# Amp_Lm386.net
KiCad netlist of a schematic drawn in Altium Designer
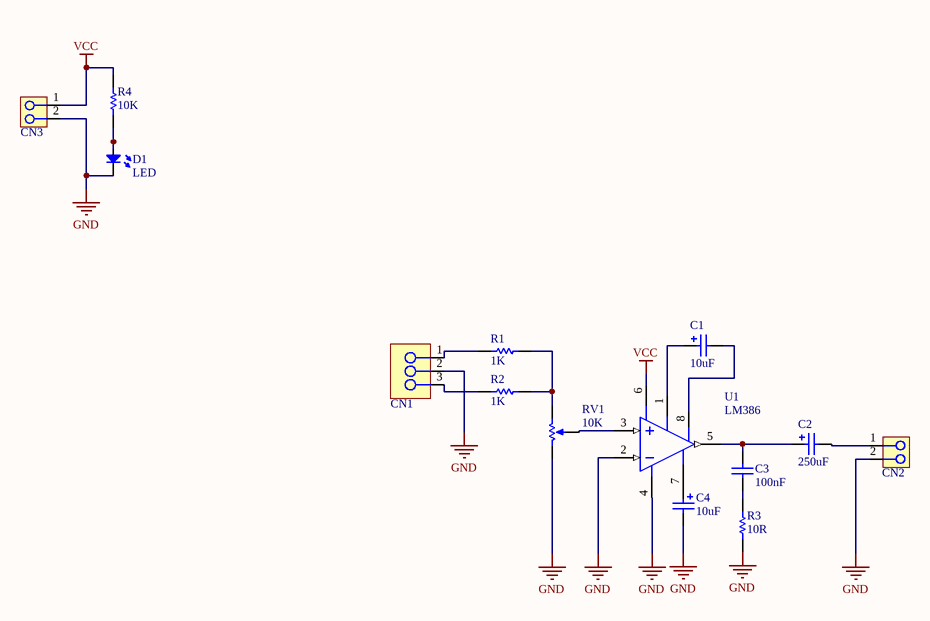
[diagram p0: Amp_Lm386.SchDoc]

(export (version "E")
  (design (tool "Eeschema 10.0.6"))
  (components
    (comp (ref "C1")
      (value "10uF")
      (footprint "Cap_1")
      (description "Capacitor Electrolytic")
      (fields
        (field (name "MANUFACTURER") "Nichicon")
        (field (name "MANUFACTURER PART NUMBER") "UCA2G100MPD1TD")
      )
      (libsource (lib "Adono_Library") (part "Cap_Eletro1"))
    )
    (comp (ref "C2")
      (value "250uF")
      (footprint "Cap_1")
      (description "Capacitor Electrolytic")
      (fields
        (field (name "MANUFACTURER") "Nichicon")
        (field (name "MANUFACTURER PART NUMBER") "UCA2G100MPD1TD")
      )
      (libsource (lib "Adono_Library") (part "Cap_Eletro1"))
    )
    (comp (ref "C3")
      (value "100nF")
      (footprint "CAP_DISC")
      (description "Capacitor Disc Ceramic")
      (fields
        (field (name "MANUFACTURER") "Multicomp")
        (field (name "MANUFACTURER PART NUMBER") "MCCC100V104KY5P")
      )
      (libsource (lib "Adono_Library") (part "Capacitor_Cerâmica"))
    )
    (comp (ref "C4")
      (value "10uF")
      (footprint "Cap_1")
      (description "Capacitor Electrolytic")
      (fields
        (field (name "MANUFACTURER") "Nichicon")
        (field (name "MANUFACTURER PART NUMBER") "UCA2G100MPD1TD")
      )
      (libsource (lib "Adono_Library") (part "Cap_Eletro1"))
    )
    (comp (ref "CN1")
      (value "H3")
      (footprint "H3")
      (description "KRE2/WD-128 3T")
      (fields
        (field (name "MANUFACTURER") "On-Shore Technology")
        (field (name "MANUFACTURER PART NUMBER") "OSTTA034163")
      )
      (libsource (lib "Adono_Library2") (part "H3"))
    )
    (comp (ref "CN2")
      (value "H2")
      (footprint "H2")
      (description "KRE2/WD-128 2T")
      (fields
        (field (name "MANUFACTURER") "On-Shore Technology")
        (field (name "MANUFACTURER PART NUMBER") "OSTTA024163")
      )
      (libsource (lib "") (part "H2_1"))
    )
    (comp (ref "CN3")
      (value "H2")
      (footprint "H2")
      (description "KRE2/WD-128 2T")
      (fields
        (field (name "MANUFACTURER") "On-Shore Technology")
        (field (name "MANUFACTURER PART NUMBER") "OSTTA024163")
      )
      (libsource (lib "Adono_Library2") (part "H2"))
    )
    (comp (ref "D1")
      (value "LED")
      (footprint "LED_GREEN")
      (description "Light Emissor Diode - 5mm")
      (fields
        (field (name "MANUFACTURER") "Kingbright")
        (field (name "MANUFACTURER PART NUMBER") "WP7113LGD")
      )
      (libsource (lib "Adono_Library2") (part "LED-GREEN"))
    )
    (comp (ref "R1")
      (value "1K")
      (footprint "Resistor")
      (description "Carbon Fiber 1/4W")
      (fields
        (field (name "MANUFACTURER") "Stackpole Electronics")
        (field (name "MANUFACTURER PART NUMBER") "CF14JT10K0")
      )
      (libsource (lib "Adono_Library") (part "Resistor"))
    )
    (comp (ref "R2")
      (value "1K")
      (footprint "Resistor")
      (description "Carbon Fiber 1/4W")
      (fields
        (field (name "MANUFACTURER") "Stackpole Electronics")
        (field (name "MANUFACTURER PART NUMBER") "CF14JT10K0")
      )
      (libsource (lib "Adono_Library") (part "Resistor"))
    )
    (comp (ref "R3")
      (value "10R")
      (footprint "Resistor")
      (description "Carbon Fiber 1/4W")
      (fields
        (field (name "MANUFACTURER") "Stackpole Electronics")
        (field (name "MANUFACTURER PART NUMBER") "CF14JT10K0")
      )
      (libsource (lib "Adono_Library") (part "Resistor"))
    )
    (comp (ref "R4")
      (value "10K")
      (footprint "Resistor")
      (description "Carbon Fiber 1/4W")
      (fields
        (field (name "MANUFACTURER") "Stackpole Electronics")
        (field (name "MANUFACTURER PART NUMBER") "CF14JT10K0")
      )
      (libsource (lib "Adono_Library2") (part "Resistor"))
    )
    (comp (ref "RV1")
      (value "10K")
      (footprint "POT PTH VERTICAL")
      (description "Potentiometer PTH Verticacl")
      (libsource (lib "Aken") (part "Potentiometer PTH Verticacl"))
    )
    (comp (ref "U1")
      (value "LM386")
      (footprint "LM386")
      (description "Amp mono")
      (libsource (lib "Aken") (part "LM386"))
    )
  )
  (nets
    (net (code "1") (name "GND") (class "Default")
      (node (ref "C4") (pin "2") (pinfunction "2_2") (pintype "passive"))
      (node (ref "CN1") (pin "2") (pinfunction "2_2") (pintype "passive"))
      (node (ref "CN2") (pin "2") (pinfunction "2_2") (pintype "passive"))
      (node (ref "CN3") (pin "2") (pinfunction "2_2") (pintype "passive"))
      (node (ref "D1") (pin "K") (pinfunction "K_K") (pintype "passive"))
      (node (ref "R3") (pin "1") (pinfunction "1_1") (pintype "passive"))
      (node (ref "RV1") (pin "3") (pinfunction "BOT_3") (pintype "passive"))
      (node (ref "U1") (pin "2") (pinfunction "IN-_2") (pintype "input"))
      (node (ref "U1") (pin "4") (pinfunction "V-_4") (pintype "power_in"))
    )
    (net (code "2") (name "Net-(C1-Pad1)") (class "Default")
      (node (ref "C1") (pin "1") (pinfunction "1_1") (pintype "passive"))
      (node (ref "U1") (pin "1") (pinfunction "GAIN_1") (pintype "power_in"))
    )
    (net (code "3") (name "Net-(C1-Pad2)") (class "Default")
      (node (ref "C1") (pin "2") (pinfunction "2_2") (pintype "passive"))
      (node (ref "U1") (pin "8") (pinfunction "GAIN_8") (pintype "power_in"))
    )
    (net (code "4") (name "Net-(C2-Pad2)") (class "Default")
      (node (ref "C2") (pin "2") (pinfunction "2_2") (pintype "passive"))
      (node (ref "CN2") (pin "1") (pinfunction "1_1") (pintype "passive"))
    )
    (net (code "5") (name "Net-(C3-Pad1)") (class "Default")
      (node (ref "C3") (pin "1") (pinfunction "1_1") (pintype "passive"))
      (node (ref "R3") (pin "2") (pinfunction "2_2") (pintype "passive"))
    )
    (net (code "6") (name "Net-(CN1-Pad1)") (class "Default")
      (node (ref "CN1") (pin "1") (pinfunction "1_1") (pintype "passive"))
      (node (ref "R1") (pin "2") (pinfunction "2_2") (pintype "passive"))
    )
    (net (code "7") (name "Net-(CN1-Pad3)") (class "Default")
      (node (ref "CN1") (pin "3") (pinfunction "3_3") (pintype "passive"))
      (node (ref "R2") (pin "2") (pinfunction "2_2") (pintype "passive"))
    )
    (net (code "8") (name "Net-(D1-PadA)") (class "Default")
      (node (ref "D1") (pin "A") (pinfunction "A_A") (pintype "passive"))
      (node (ref "R4") (pin "1") (pinfunction "1_1") (pintype "passive"))
    )
    (net (code "9") (name "Net-(RV1-TAP)") (class "Default")
      (node (ref "RV1") (pin "2") (pinfunction "TAP_2") (pintype "passive"))
      (node (ref "U1") (pin "3") (pinfunction "IN+_3") (pintype "input"))
    )
    (net (code "10") (name "Net-(RV1-TOP)") (class "Default")
      (node (ref "R1") (pin "1") (pinfunction "1_1") (pintype "passive"))
      (node (ref "R2") (pin "1") (pinfunction "1_1") (pintype "passive"))
      (node (ref "RV1") (pin "1") (pinfunction "TOP_1") (pintype "passive"))
    )
    (net (code "11") (name "Net-(U1-BYPASS)") (class "Default")
      (node (ref "C4") (pin "1") (pinfunction "1_1") (pintype "passive"))
      (node (ref "U1") (pin "7") (pinfunction "BYPASS_7") (pintype "power_in"))
    )
    (net (code "12") (name "Net-(U1-OUT)") (class "Default")
      (node (ref "C2") (pin "1") (pinfunction "1_1") (pintype "passive"))
      (node (ref "C3") (pin "2") (pinfunction "2_2") (pintype "passive"))
      (node (ref "U1") (pin "5") (pinfunction "OUT_5") (pintype "output"))
    )
    (net (code "13") (name "VCC") (class "Default")
      (node (ref "CN3") (pin "1") (pinfunction "1_1") (pintype "passive"))
      (node (ref "R4") (pin "2") (pinfunction "2_2") (pintype "passive"))
      (node (ref "U1") (pin "6") (pinfunction "V+_6") (pintype "power_in"))
    )
  )
)
